# Temperature_Sense.net
KiCad netlist of a schematic drawn in Altium Designer
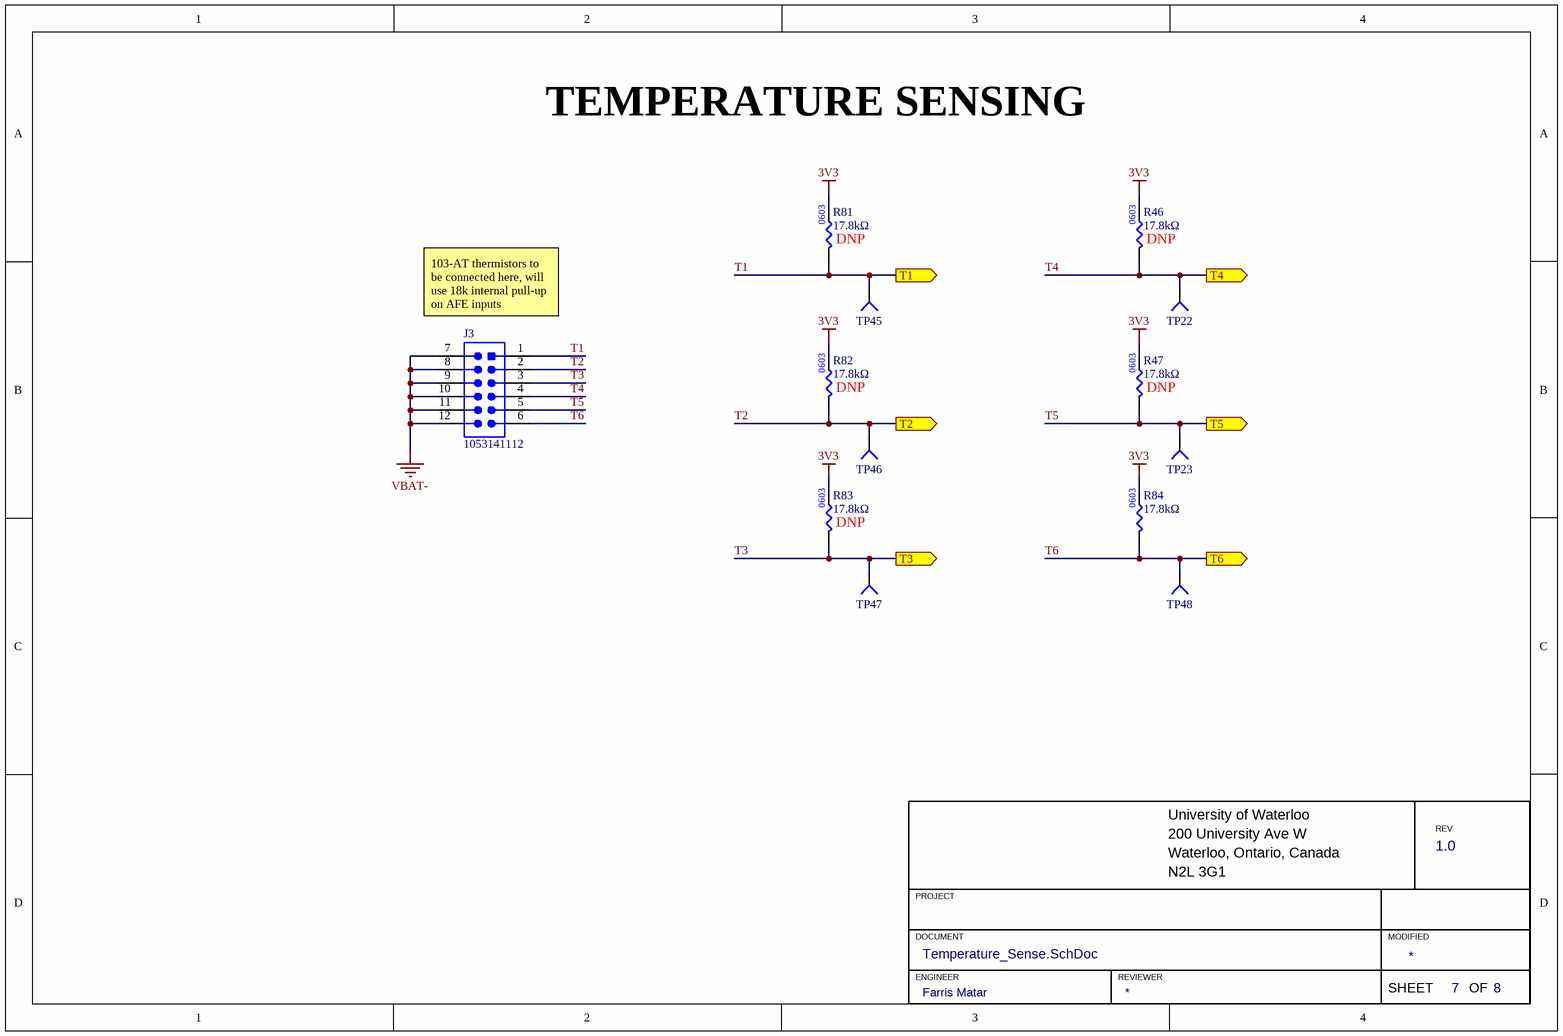
[diagram p0: Temperature_Sense.SchDoc]

(export (version "E")
  (design (tool "Eeschema 10.0.6"))
  (components
    (comp (ref "J3")
      (value "1053141112")
      (footprint "MOLEX-NANOFIT 6x2 THRA")
      (description "CONN HEADER R/A 12POS 2.5MM")
      (fields (field (name "MANUFACTURER PART NUMBER 1") "1053141112"))
      (libsource (lib "Personal_Schematic_Library_2022") (part "CON_MOLEX-NANOFIT_6x2_THRA"))
    )
    (comp (ref "R46")
      (value "17.8kΩ")
      (footprint "RES0603")
      (description "RES 17.8K OHM 1% 1/10W 0603")
      (fields (field (name "Comment") "RES_17.8kΩ_0603_1%"))
      (libsource (lib "Personal_Schematic_Library_2022") (part "RES_17.8kΩ_0603_1%"))
    )
    (comp (ref "R47")
      (value "17.8kΩ")
      (footprint "RES0603")
      (description "RES 17.8K OHM 1% 1/10W 0603")
      (fields (field (name "Comment") "RES_17.8kΩ_0603_1%"))
      (libsource (lib "Personal_Schematic_Library_2022") (part "RES_17.8kΩ_0603_1%"))
    )
    (comp (ref "R81")
      (value "17.8kΩ")
      (footprint "RES0603")
      (description "RES 17.8K OHM 1% 1/10W 0603")
      (fields (field (name "Comment") "RES_17.8kΩ_0603_1%"))
      (libsource (lib "Personal_Schematic_Library_2022") (part "RES_17.8kΩ_0603_1%"))
    )
    (comp (ref "R82")
      (value "17.8kΩ")
      (footprint "RES0603")
      (description "RES 17.8K OHM 1% 1/10W 0603")
      (fields (field (name "Comment") "RES_17.8kΩ_0603_1%"))
      (libsource (lib "Personal_Schematic_Library_2022") (part "RES_17.8kΩ_0603_1%"))
    )
    (comp (ref "R83")
      (value "17.8kΩ")
      (footprint "RES0603")
      (description "RES 17.8K OHM 1% 1/10W 0603")
      (fields (field (name "Comment") "RES_17.8kΩ_0603_1%"))
      (libsource (lib "Personal_Schematic_Library_2022") (part "RES_17.8kΩ_0603_1%"))
    )
    (comp (ref "R84")
      (value "17.8kΩ")
      (footprint "RES0603")
      (description "RES 17.8K OHM 1% 1/10W 0603")
      (fields (field (name "Comment") "RES_17.8kΩ_0603_1%"))
      (libsource (lib "Personal_Schematic_Library_2022") (part "RES_17.8kΩ_0603_1%"))
    )
    (comp (ref "TP22")
      (value "TESTPOINT_1MM_CIRCLE")
      (footprint "TESTPOINT_CIRCLE_1MM")
      (description "TESTPOINT 1MM CIRCLE")
      (libsource (lib "Personal_Schematic_Library_2022") (part "TESTPOINT_1MM_CIRCLE"))
    )
    (comp (ref "TP23")
      (value "TESTPOINT_1MM_CIRCLE")
      (footprint "TESTPOINT_CIRCLE_1MM")
      (description "TESTPOINT 1MM CIRCLE")
      (libsource (lib "Personal_Schematic_Library_2022") (part "TESTPOINT_1MM_CIRCLE"))
    )
    (comp (ref "TP45")
      (value "TESTPOINT_1MM_CIRCLE")
      (footprint "TESTPOINT_CIRCLE_1MM")
      (description "TESTPOINT 1MM CIRCLE")
      (libsource (lib "Personal_Schematic_Library_2022") (part "TESTPOINT_1MM_CIRCLE"))
    )
    (comp (ref "TP46")
      (value "TESTPOINT_1MM_CIRCLE")
      (footprint "TESTPOINT_CIRCLE_1MM")
      (description "TESTPOINT 1MM CIRCLE")
      (libsource (lib "Personal_Schematic_Library_2022") (part "TESTPOINT_1MM_CIRCLE"))
    )
    (comp (ref "TP47")
      (value "TESTPOINT_1MM_CIRCLE")
      (footprint "TESTPOINT_CIRCLE_1MM")
      (description "TESTPOINT 1MM CIRCLE")
      (libsource (lib "Personal_Schematic_Library_2022") (part "TESTPOINT_1MM_CIRCLE"))
    )
    (comp (ref "TP48")
      (value "TESTPOINT_1MM_CIRCLE")
      (footprint "TESTPOINT_CIRCLE_1MM")
      (description "TESTPOINT 1MM CIRCLE")
      (libsource (lib "Personal_Schematic_Library_2022") (part "TESTPOINT_1MM_CIRCLE"))
    )
  )
  (nets
    (net (code "1") (name "/T1") (class "Default")
      (node (ref "J3") (pin "1") (pinfunction "1_1") (pintype "passive"))
      (node (ref "R81") (pin "1") (pinfunction "1_1") (pintype "passive"))
      (node (ref "TP45") (pin "1") (pinfunction "=value_1") (pintype "passive"))
    )
    (net (code "2") (name "/T2") (class "Default")
      (node (ref "J3") (pin "2") (pinfunction "2_2") (pintype "passive"))
      (node (ref "R82") (pin "1") (pinfunction "1_1") (pintype "passive"))
      (node (ref "TP46") (pin "1") (pinfunction "=value_1") (pintype "passive"))
    )
    (net (code "3") (name "/T3") (class "Default")
      (node (ref "J3") (pin "3") (pinfunction "3_3") (pintype "passive"))
      (node (ref "R83") (pin "1") (pinfunction "1_1") (pintype "passive"))
      (node (ref "TP47") (pin "1") (pinfunction "=value_1") (pintype "passive"))
    )
    (net (code "4") (name "/T4") (class "Default")
      (node (ref "J3") (pin "4") (pinfunction "4_4") (pintype "passive"))
      (node (ref "R46") (pin "1") (pinfunction "1_1") (pintype "passive"))
      (node (ref "TP22") (pin "1") (pinfunction "=value_1") (pintype "passive"))
    )
    (net (code "5") (name "/T5") (class "Default")
      (node (ref "J3") (pin "5") (pinfunction "5_5") (pintype "passive"))
      (node (ref "R47") (pin "1") (pinfunction "1_1") (pintype "passive"))
      (node (ref "TP23") (pin "1") (pinfunction "=value_1") (pintype "passive"))
    )
    (net (code "6") (name "/T6") (class "Default")
      (node (ref "J3") (pin "6") (pinfunction "6_6") (pintype "passive"))
      (node (ref "R84") (pin "1") (pinfunction "1_1") (pintype "passive"))
      (node (ref "TP48") (pin "1") (pinfunction "=value_1") (pintype "passive"))
    )
    (net (code "7") (name "3V3") (class "Default")
      (node (ref "R46") (pin "2") (pinfunction "2_2") (pintype "passive"))
      (node (ref "R47") (pin "2") (pinfunction "2_2") (pintype "passive"))
      (node (ref "R81") (pin "2") (pinfunction "2_2") (pintype "passive"))
      (node (ref "R82") (pin "2") (pinfunction "2_2") (pintype "passive"))
      (node (ref "R83") (pin "2") (pinfunction "2_2") (pintype "passive"))
      (node (ref "R84") (pin "2") (pinfunction "2_2") (pintype "passive"))
    )
    (net (code "8") (name "VBAT-") (class "Default")
      (node (ref "J3") (pin "10") (pinfunction "10_10") (pintype "passive"))
      (node (ref "J3") (pin "11") (pinfunction "11_11") (pintype "passive"))
      (node (ref "J3") (pin "12") (pinfunction "12_12") (pintype "passive"))
      (node (ref "J3") (pin "7") (pinfunction "7_7") (pintype "passive"))
      (node (ref "J3") (pin "8") (pinfunction "8_8") (pintype "passive"))
      (node (ref "J3") (pin "9") (pinfunction "9_9") (pintype "passive"))
    )
  )
)
